# SUP_1V.net
KiCad netlist of a schematic drawn in Altium Designer
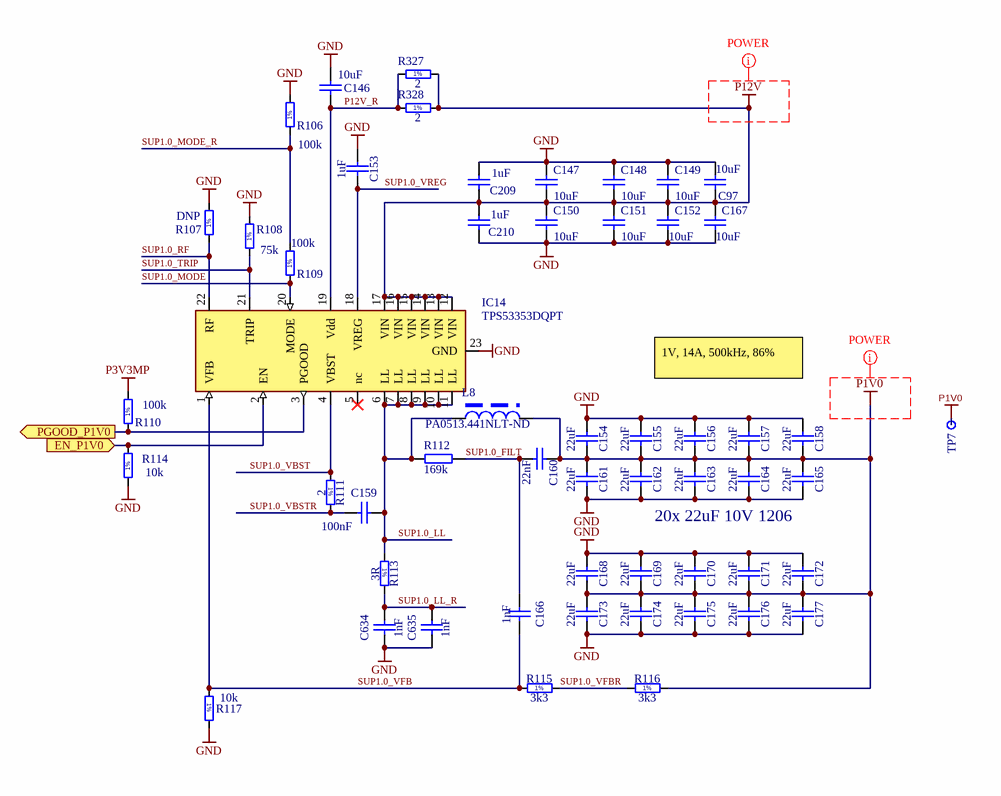
[diagram p0: SUP_1V.SchDoc]

(export (version "E")
  (design (tool "Eeschema 10.0.6"))
  (components
    (comp (ref "C97")
      (value "10uF")
      (footprint "CAPC2012X135N")
      (description "Non-polarised capacitor")
      (fields
        (field (name "PART NUMBER") "CC0805_10UF_16V_10%_X5R")
        (field (name "VOLTAGE") "16V")
        (field (name "AUTHOR") "CERN DEM JLC")
      )
      (libsource (lib "Capacitors") (part "Capacitor - non polarized"))
    )
    (comp (ref "C146")
      (value "10uF")
      (footprint "CAPC2012X135N")
      (description "Non-polarised capacitor")
      (fields
        (field (name "PART NUMBER") "CC0805_10UF_16V_10%_X5R")
        (field (name "VOLTAGE") "16V")
        (field (name "AUTHOR") "CERN DEM JLC")
      )
      (libsource (lib "Capacitors") (part "Capacitor - non polarized"))
    )
    (comp (ref "C147")
      (value "10uF")
      (footprint "CAPC2012X135N")
      (description "Non-polarised capacitor")
      (fields
        (field (name "PART NUMBER") "CC0805_10UF_16V_10%_X5R")
        (field (name "VOLTAGE") "16V")
        (field (name "AUTHOR") "CERN DEM JLC")
      )
      (libsource (lib "Capacitors") (part "Capacitor - non polarized"))
    )
    (comp (ref "C148")
      (value "10uF")
      (footprint "CAPC2012X135N")
      (description "Non-polarised capacitor")
      (fields
        (field (name "PART NUMBER") "CC0805_10UF_16V_10%_X5R")
        (field (name "VOLTAGE") "16V")
        (field (name "AUTHOR") "CERN DEM JLC")
      )
      (libsource (lib "Capacitors") (part "Capacitor - non polarized"))
    )
    (comp (ref "C149")
      (value "10uF")
      (footprint "CAPC2012X135N")
      (description "Non-polarised capacitor")
      (fields
        (field (name "PART NUMBER") "CC0805_10UF_16V_10%_X5R")
        (field (name "VOLTAGE") "16V")
        (field (name "AUTHOR") "CERN DEM JLC")
      )
      (libsource (lib "Capacitors") (part "Capacitor - non polarized"))
    )
    (comp (ref "C150")
      (value "10uF")
      (footprint "CAPC2012X135N")
      (description "Non-polarised capacitor")
      (fields
        (field (name "PART NUMBER") "CC0805_10UF_16V_10%_X5R")
        (field (name "VOLTAGE") "16V")
        (field (name "AUTHOR") "CERN DEM JLC")
      )
      (libsource (lib "Capacitors") (part "Capacitor - non polarized"))
    )
    (comp (ref "C151")
      (value "10uF")
      (footprint "CAPC2012X135N")
      (description "Non-polarised capacitor")
      (fields
        (field (name "PART NUMBER") "CC0805_10UF_16V_10%_X5R")
        (field (name "VOLTAGE") "16V")
        (field (name "AUTHOR") "CERN DEM JLC")
      )
      (libsource (lib "Capacitors") (part "Capacitor - non polarized"))
    )
    (comp (ref "C152")
      (value "10uF")
      (footprint "CAPC2012X135N")
      (description "Non-polarised capacitor")
      (fields
        (field (name "PART NUMBER") "CC0805_10UF_16V_10%_X5R")
        (field (name "VOLTAGE") "16V")
        (field (name "AUTHOR") "CERN DEM JLC")
      )
      (libsource (lib "Capacitors") (part "Capacitor - non polarized"))
    )
    (comp (ref "C153")
      (value "1uF")
      (footprint "CAPC1608X87N")
      (description "Non-polarised capacitor")
      (fields
        (field (name "PART NUMBER") "CC0603_1UF_16V_10%_X7R")
        (field (name "VOLTAGE") "16V")
        (field (name "AUTHOR") "CERN DEM JLC")
      )
      (libsource (lib "Capacitors") (part "Capacitor - non polarized"))
    )
    (comp (ref "C154")
      (value "22uF")
      (footprint "CAPC3216X180N")
      (description "Non-polarised capacitor")
      (fields
        (field (name "PART NUMBER") "CC1206_22UF_10V_10%_X7R")
        (field (name "VOLTAGE") "10V")
        (field (name "AUTHOR") "CERN DEM JLC")
      )
      (libsource (lib "Capacitors") (part "Capacitor - non polarized"))
    )
    (comp (ref "C155")
      (value "22uF")
      (footprint "CAPC3216X180N")
      (description "Non-polarised capacitor")
      (fields
        (field (name "PART NUMBER") "CC1206_22UF_10V_10%_X7R")
        (field (name "VOLTAGE") "10V")
        (field (name "AUTHOR") "CERN DEM JLC")
      )
      (libsource (lib "Capacitors") (part "Capacitor - non polarized"))
    )
    (comp (ref "C156")
      (value "22uF")
      (footprint "CAPC3216X180N")
      (description "Non-polarised capacitor")
      (fields
        (field (name "PART NUMBER") "CC1206_22UF_10V_10%_X7R")
        (field (name "VOLTAGE") "10V")
        (field (name "AUTHOR") "CERN DEM JLC")
      )
      (libsource (lib "Capacitors") (part "Capacitor - non polarized"))
    )
    (comp (ref "C157")
      (value "22uF")
      (footprint "CAPC3216X180N")
      (description "Non-polarised capacitor")
      (fields
        (field (name "PART NUMBER") "CC1206_22UF_10V_10%_X7R")
        (field (name "VOLTAGE") "10V")
        (field (name "AUTHOR") "CERN DEM JLC")
      )
      (libsource (lib "Capacitors") (part "Capacitor - non polarized"))
    )
    (comp (ref "C158")
      (value "22uF")
      (footprint "CAPC3216X180N")
      (description "Non-polarised capacitor")
      (fields
        (field (name "PART NUMBER") "CC1206_22UF_10V_10%_X7R")
        (field (name "VOLTAGE") "10V")
        (field (name "AUTHOR") "CERN DEM JLC")
      )
      (libsource (lib "Capacitors") (part "Capacitor - non polarized"))
    )
    (comp (ref "C159")
      (value "100nF")
      (footprint "CAPC1005X55N")
      (description "Non-polarised capacitor")
      (fields
        (field (name "PART NUMBER") "CC0402_100NF_16V_10%_X7R")
        (field (name "VOLTAGE") "16V")
        (field (name "AUTHOR") "CERN DEM JLC")
      )
      (libsource (lib "Capacitors") (part "Capacitor - non polarized"))
    )
    (comp (ref "C160")
      (value "22nF")
      (footprint "CAPC1608X87N")
      (description "Non-polarised capacitor")
      (fields
        (field (name "PART NUMBER") "CC0603_22NF_50V_10%_X7R")
        (field (name "VOLTAGE") "50V")
        (field (name "AUTHOR") "CERN DEM JLC")
      )
      (libsource (lib "Capacitors") (part "Capacitor - non polarized"))
    )
    (comp (ref "C161")
      (value "22uF")
      (footprint "CAPC3216X180N")
      (description "Non-polarised capacitor")
      (fields
        (field (name "PART NUMBER") "CC1206_22UF_10V_10%_X7R")
        (field (name "VOLTAGE") "10V")
        (field (name "AUTHOR") "CERN DEM JLC")
      )
      (libsource (lib "Capacitors") (part "Capacitor - non polarized"))
    )
    (comp (ref "C162")
      (value "22uF")
      (footprint "CAPC3216X180N")
      (description "Non-polarised capacitor")
      (fields
        (field (name "PART NUMBER") "CC1206_22UF_10V_10%_X7R")
        (field (name "VOLTAGE") "10V")
        (field (name "AUTHOR") "CERN DEM JLC")
      )
      (libsource (lib "Capacitors") (part "Capacitor - non polarized"))
    )
    (comp (ref "C163")
      (value "22uF")
      (footprint "CAPC3216X180N")
      (description "Non-polarised capacitor")
      (fields
        (field (name "PART NUMBER") "CC1206_22UF_10V_10%_X7R")
        (field (name "VOLTAGE") "10V")
        (field (name "AUTHOR") "CERN DEM JLC")
      )
      (libsource (lib "Capacitors") (part "Capacitor - non polarized"))
    )
    (comp (ref "C164")
      (value "22uF")
      (footprint "CAPC3216X180N")
      (description "Non-polarised capacitor")
      (fields
        (field (name "PART NUMBER") "CC1206_22UF_10V_10%_X7R")
        (field (name "VOLTAGE") "10V")
        (field (name "AUTHOR") "CERN DEM JLC")
      )
      (libsource (lib "Capacitors") (part "Capacitor - non polarized"))
    )
    (comp (ref "C165")
      (value "22uF")
      (footprint "CAPC3216X180N")
      (description "Non-polarised capacitor")
      (fields
        (field (name "PART NUMBER") "CC1206_22UF_10V_10%_X7R")
        (field (name "VOLTAGE") "10V")
        (field (name "AUTHOR") "CERN DEM JLC")
      )
      (libsource (lib "Capacitors") (part "Capacitor - non polarized"))
    )
    (comp (ref "C166")
      (value "1nF")
      (footprint "CAPC1005X55N")
      (description "Non-polarised capacitor")
      (fields
        (field (name "PART NUMBER") "CC0402_1NF_50V_10%_X7R")
        (field (name "VOLTAGE") "50V")
        (field (name "AUTHOR") "CERN DEM JLC")
      )
      (libsource (lib "Capacitors") (part "Capacitor - non polarized"))
    )
    (comp (ref "C167")
      (value "10uF")
      (footprint "CAPC2012X135N")
      (description "Non-polarised capacitor")
      (fields
        (field (name "PART NUMBER") "CC0805_10UF_16V_10%_X5R")
        (field (name "VOLTAGE") "16V")
        (field (name "AUTHOR") "CERN DEM JLC")
      )
      (libsource (lib "Capacitors") (part "Capacitor - non polarized"))
    )
    (comp (ref "C168")
      (value "22uF")
      (footprint "CAPC3216X180N")
      (description "Non-polarised capacitor")
      (fields
        (field (name "PART NUMBER") "CC1206_22UF_10V_10%_X7R")
        (field (name "VOLTAGE") "10V")
        (field (name "AUTHOR") "CERN DEM JLC")
      )
      (libsource (lib "Capacitors") (part "Capacitor - non polarized"))
    )
    (comp (ref "C169")
      (value "22uF")
      (footprint "CAPC3216X180N")
      (description "Non-polarised capacitor")
      (fields
        (field (name "PART NUMBER") "CC1206_22UF_10V_10%_X7R")
        (field (name "VOLTAGE") "10V")
        (field (name "AUTHOR") "CERN DEM JLC")
      )
      (libsource (lib "Capacitors") (part "Capacitor - non polarized"))
    )
    (comp (ref "C170")
      (value "22uF")
      (footprint "CAPC3216X180N")
      (description "Non-polarised capacitor")
      (fields
        (field (name "PART NUMBER") "CC1206_22UF_10V_10%_X7R")
        (field (name "VOLTAGE") "10V")
        (field (name "AUTHOR") "CERN DEM JLC")
      )
      (libsource (lib "Capacitors") (part "Capacitor - non polarized"))
    )
    (comp (ref "C171")
      (value "22uF")
      (footprint "CAPC3216X180N")
      (description "Non-polarised capacitor")
      (fields
        (field (name "PART NUMBER") "CC1206_22UF_10V_10%_X7R")
        (field (name "VOLTAGE") "10V")
        (field (name "AUTHOR") "CERN DEM JLC")
      )
      (libsource (lib "Capacitors") (part "Capacitor - non polarized"))
    )
    (comp (ref "C172")
      (value "22uF")
      (footprint "CAPC3216X180N")
      (description "Non-polarised capacitor")
      (fields
        (field (name "PART NUMBER") "CC1206_22UF_10V_10%_X7R")
        (field (name "VOLTAGE") "10V")
        (field (name "AUTHOR") "CERN DEM JLC")
      )
      (libsource (lib "Capacitors") (part "Capacitor - non polarized"))
    )
    (comp (ref "C173")
      (value "22uF")
      (footprint "CAPC3216X180N")
      (description "Non-polarised capacitor")
      (fields
        (field (name "PART NUMBER") "CC1206_22UF_10V_10%_X7R")
        (field (name "VOLTAGE") "10V")
        (field (name "AUTHOR") "CERN DEM JLC")
      )
      (libsource (lib "Capacitors") (part "Capacitor - non polarized"))
    )
    (comp (ref "C174")
      (value "22uF")
      (footprint "CAPC3216X180N")
      (description "Non-polarised capacitor")
      (fields
        (field (name "PART NUMBER") "CC1206_22UF_10V_10%_X7R")
        (field (name "VOLTAGE") "10V")
        (field (name "AUTHOR") "CERN DEM JLC")
      )
      (libsource (lib "Capacitors") (part "Capacitor - non polarized"))
    )
    (comp (ref "C175")
      (value "22uF")
      (footprint "CAPC3216X180N")
      (description "Non-polarised capacitor")
      (fields
        (field (name "PART NUMBER") "CC1206_22UF_10V_10%_X7R")
        (field (name "VOLTAGE") "10V")
        (field (name "AUTHOR") "CERN DEM JLC")
      )
      (libsource (lib "Capacitors") (part "Capacitor - non polarized"))
    )
    (comp (ref "C176")
      (value "22uF")
      (footprint "CAPC3216X180N")
      (description "Non-polarised capacitor")
      (fields
        (field (name "PART NUMBER") "CC1206_22UF_10V_10%_X7R")
        (field (name "VOLTAGE") "10V")
        (field (name "AUTHOR") "CERN DEM JLC")
      )
      (libsource (lib "Capacitors") (part "Capacitor - non polarized"))
    )
    (comp (ref "C177")
      (value "22uF")
      (footprint "CAPC3216X180N")
      (description "Non-polarised capacitor")
      (fields
        (field (name "PART NUMBER") "CC1206_22UF_10V_10%_X7R")
        (field (name "VOLTAGE") "10V")
        (field (name "AUTHOR") "CERN DEM JLC")
      )
      (libsource (lib "Capacitors") (part "Capacitor - non polarized"))
    )
    (comp (ref "C209")
      (value "1uF")
      (footprint "CAPC1608X87N")
      (description "Non-polarised capacitor")
      (fields
        (field (name "PART NUMBER") "CC0603_1UF_16V_10%_X7R")
        (field (name "VOLTAGE") "16V")
        (field (name "AUTHOR") "CERN DEM JLC")
      )
      (libsource (lib "Capacitors") (part "Capacitor - non polarized"))
    )
    (comp (ref "C210")
      (value "1uF")
      (footprint "CAPC1608X87N")
      (description "Non-polarised capacitor")
      (fields
        (field (name "PART NUMBER") "CC0603_1UF_16V_10%_X7R")
        (field (name "VOLTAGE") "16V")
        (field (name "AUTHOR") "CERN DEM JLC")
      )
      (libsource (lib "Capacitors") (part "Capacitor - non polarized"))
    )
    (comp (ref "C634")
      (value "1nF")
      (footprint "CAPC1005X55N")
      (description "Non-polarised capacitor")
      (fields
        (field (name "PART NUMBER") "CC0402_1NF_50V_10%_X7R")
        (field (name "VOLTAGE") "50V")
        (field (name "AUTHOR") "CERN DEM JLC")
      )
      (libsource (lib "Capacitors") (part "Capacitor - non polarized"))
    )
    (comp (ref "C635")
      (value "1nF")
      (footprint "CAPC1005X55N")
      (description "Non-polarised capacitor")
      (fields
        (field (name "PART NUMBER") "CC0402_1NF_50V_10%_X7R")
        (field (name "VOLTAGE") "50V")
        (field (name "AUTHOR") "CERN DEM JLC")
      )
      (libsource (lib "Capacitors") (part "Capacitor - non polarized"))
    )
    (comp (ref "IC14")
      (value "TPS53353DQPT")
      (footprint "LCCS50P600X500X150-22N")
      (description "High-Efficiency 20-A Synchronous Buck Converter with Eco-mode™")
      (libsource (lib "LIBRARY_SCH") (part "PM_TPS53353"))
    )
    (comp (ref "L8")
      (value "PA0513.441NLT-ND")
      (footprint "IND_PA0513")
      (description "440nH, 30A, 0.32mOhm")
      (libsource (lib "LIBRARY_SCH") (part "L_POWER_PA1513_440nH"))
    )
    (comp (ref "R106")
      (value "100k")
      (footprint "RESC1005X40N")
      (description "Resistor - 1%")
      (fields
        (field (name "PART NUMBER") "R0402_100K_1%_0.0625W_100PPM")
        (field (name "POWER") "0.0625W")
        (field (name "AUTHOR") "CERN DEM JLC")
      )
      (libsource (lib "Resistors") (part "Resistor - 1%"))
    )
    (comp (ref "R107")
      (value "DNP")
      (footprint "RESC1608X55N")
      (description "Resistor - 1%")
      (fields
        (field (name "PART NUMBER") "R0603_75K_1%_0.1W_100PPM")
        (field (name "POWER") "0.1W")
        (field (name "AUTHOR") "CERN DEM JLC")
      )
      (libsource (lib "Resistors") (part "Resistor - 1%"))
    )
    (comp (ref "R108")
      (value "75k")
      (footprint "RESC1608X55N")
      (description "Resistor - 1%")
      (fields
        (field (name "PART NUMBER") "R0603_75K_1%_0.1W_100PPM")
        (field (name "POWER") "0.1W")
        (field (name "AUTHOR") "CERN DEM JLC")
      )
      (libsource (lib "Resistors") (part "Resistor - 1%"))
    )
    (comp (ref "R109")
      (value "100k")
      (footprint "RESC1005X40N")
      (description "Resistor - 1%")
      (fields
        (field (name "PART NUMBER") "R0402_100K_1%_0.0625W_100PPM")
        (field (name "POWER") "0.0625W")
        (field (name "AUTHOR") "CERN DEM JLC")
      )
      (libsource (lib "Resistors") (part "Resistor - 1%"))
    )
    (comp (ref "R110")
      (value "100k")
      (footprint "RESC1005X40N")
      (description "Resistor - 1%")
      (fields
        (field (name "PART NUMBER") "R0402_100K_1%_0.0625W_100PPM")
        (field (name "POWER") "0.0625W")
        (field (name "AUTHOR") "CERN DEM JLC")
      )
      (libsource (lib "Resistors") (part "Resistor - 1%"))
    )
    (comp (ref "R111")
      (value "2")
      (footprint "RESC1608X55N")
      (description "Resistor - 1%")
      (fields
        (field (name "PART NUMBER") "R0603_2R_1%_0.1W_200PPM")
        (field (name "POWER") "0.1W")
        (field (name "AUTHOR") "CERN DEM JLC")
      )
      (libsource (lib "Resistors") (part "Resistor - 1%"))
    )
    (comp (ref "R112")
      (value "169k")
      (footprint "0603R")
      (description "SMD Resistor")
      (libsource (lib "LIBRARY_SCH") (part "RES_0603"))
    )
    (comp (ref "R113")
      (value "3R")
      (footprint "RESC3216X65N")
      (description "Resistor - 1%")
      (fields
        (field (name "PART NUMBER") "R1206_3R_1%_0.25W_200PPM")
        (field (name "POWER") "0.25W")
        (field (name "AUTHOR") "CERN DEM JLC")
      )
      (libsource (lib "Resistors") (part "Resistor - 1%"))
    )
    (comp (ref "R114")
      (value "10k")
      (footprint "RESC1005X40N")
      (description "Resistor - 1%")
      (fields
        (field (name "PART NUMBER") "R0402_10K_1%_0.0625W_100PPM")
        (field (name "POWER") "0.0625W")
        (field (name "AUTHOR") "CERN DEM JLC")
      )
      (libsource (lib "Resistors") (part "Resistor - 1%"))
    )
    (comp (ref "R115")
      (value "3k3")
      (footprint "RESC1608X55N")
      (description "Resistor - 1%")
      (fields
        (field (name "PART NUMBER") "R0603_3K3_1%_0.1W_100PPM")
        (field (name "POWER") "0.1W")
        (field (name "AUTHOR") "CERN DEM JLC")
      )
      (libsource (lib "Resistors") (part "Resistor - 1%"))
    )
    (comp (ref "R116")
      (value "3k3")
      (footprint "RESC1608X55N")
      (description "Resistor - 1%")
      (fields
        (field (name "PART NUMBER") "R0603_3K3_1%_0.1W_100PPM")
        (field (name "POWER") "0.1W")
        (field (name "AUTHOR") "CERN DEM JLC")
      )
      (libsource (lib "Resistors") (part "Resistor - 1%"))
    )
    (comp (ref "R117")
      (value "10k")
      (footprint "RESC1005X40N")
      (description "Resistor - 1%")
      (fields
        (field (name "PART NUMBER") "R0402_10K_1%_0.0625W_100PPM")
        (field (name "POWER") "0.0625W")
        (field (name "AUTHOR") "CERN DEM JLC")
      )
      (libsource (lib "Resistors") (part "Resistor - 1%"))
    )
    (comp (ref "R327")
      (value "2")
      (footprint "RESC1608X55N")
      (description "Resistor - 1%")
      (fields
        (field (name "PART NUMBER") "R0603_2R_1%_0.1W_200PPM")
        (field (name "POWER") "0.1W")
        (field (name "AUTHOR") "CERN DEM JLC")
      )
      (libsource (lib "Resistors") (part "Resistor - 1%"))
    )
    (comp (ref "R328")
      (value "2")
      (footprint "RESC1608X55N")
      (description "Resistor - 1%")
      (fields
        (field (name "PART NUMBER") "R0603_2R_1%_0.1W_200PPM")
        (field (name "POWER") "0.1W")
        (field (name "AUTHOR") "CERN DEM JLC")
      )
      (libsource (lib "Resistors") (part "Resistor - 1%"))
    )
    (comp (ref "TP7")
      (value "Test Point")
      (footprint "TPS127")
      (fields (field (name "PART NUMBER") "SMD_PAD_1.27X1.27MM") (field (name "AUTHOR") "CERN DEM JLC"))
      (libsource (lib "Eletro-mechanical") (part "Test Point"))
    )
  )
  (nets
    (net (code "1") (name "/EN_P1V0") (class "Default")
      (node (ref "IC14") (pin "2") (pinfunction "EN_2") (pintype "input"))
      (node (ref "R114") (pin "2") (pinfunction "2_2") (pintype "passive"))
    )
    (net (code "2") (name "/P12V_R") (class "Default")
      (node (ref "C146") (pin "1") (pinfunction "1_1") (pintype "passive"))
      (node (ref "IC14") (pin "19") (pinfunction "Vdd_19") (pintype "power_in"))
      (node (ref "R327") (pin "1") (pinfunction "1_1") (pintype "passive"))
      (node (ref "R328") (pin "1") (pinfunction "1_1") (pintype "passive"))
    )
    (net (code "3") (name "/PGOOD_P1V0") (class "Default")
      (node (ref "IC14") (pin "3") (pinfunction "PGOOD_3") (pintype "output"))
      (node (ref "R110") (pin "1") (pinfunction "1_1") (pintype "passive"))
    )
    (net (code "4") (name "/SUP1.0_FILT") (class "Default")
      (node (ref "C160") (pin "1") (pinfunction "1_1") (pintype "passive"))
      (node (ref "C166") (pin "2") (pinfunction "2_2") (pintype "passive"))
      (node (ref "R112") (pin "1") (pinfunction "1_1") (pintype "passive"))
    )
    (net (code "5") (name "/SUP1.0_LL") (class "Default")
      (node (ref "C159") (pin "1") (pinfunction "1_1") (pintype "passive"))
      (node (ref "IC14") (pin "10") (pinfunction "LL_10") (pintype "passive"))
      (node (ref "IC14") (pin "11") (pinfunction "LL_11") (pintype "passive"))
      (node (ref "IC14") (pin "6") (pinfunction "LL_6") (pintype "passive"))
      (node (ref "IC14") (pin "7") (pinfunction "LL_7") (pintype "passive"))
      (node (ref "IC14") (pin "8") (pinfunction "LL_8") (pintype "passive"))
      (node (ref "IC14") (pin "9") (pinfunction "LL_9") (pintype "passive"))
      (node (ref "L8") (pin "1") (pintype "passive"))
      (node (ref "R112") (pin "2") (pinfunction "2_2") (pintype "passive"))
      (node (ref "R113") (pin "1") (pinfunction "1_1") (pintype "passive"))
    )
    (net (code "6") (name "/SUP1.0_LL_R") (class "Default")
      (node (ref "C634") (pin "1") (pinfunction "1_1") (pintype "passive"))
      (node (ref "C635") (pin "1") (pinfunction "1_1") (pintype "passive"))
      (node (ref "R113") (pin "2") (pinfunction "2_2") (pintype "passive"))
    )
    (net (code "7") (name "/SUP1.0_MODE") (class "Default")
      (node (ref "IC14") (pin "20") (pinfunction "MODE_20") (pintype "input"))
      (node (ref "R109") (pin "1") (pinfunction "1_1") (pintype "passive"))
    )
    (net (code "8") (name "/SUP1.0_MODE_R") (class "Default")
      (node (ref "R106") (pin "1") (pinfunction "1_1") (pintype "passive"))
      (node (ref "R109") (pin "2") (pinfunction "2_2") (pintype "passive"))
    )
    (net (code "9") (name "/SUP1.0_RF") (class "Default")
      (node (ref "IC14") (pin "22") (pinfunction "RF_22") (pintype "passive"))
      (node (ref "R107") (pin "1") (pinfunction "1_1") (pintype "passive"))
    )
    (net (code "10") (name "/SUP1.0_TRIP") (class "Default")
      (node (ref "IC14") (pin "21") (pinfunction "TRIP_21") (pintype "passive"))
      (node (ref "R108") (pin "1") (pinfunction "1_1") (pintype "passive"))
    )
    (net (code "11") (name "/SUP1.0_VBST") (class "Default")
      (node (ref "IC14") (pin "4") (pinfunction "VBST_4") (pintype "passive"))
      (node (ref "R111") (pin "1") (pinfunction "1_1") (pintype "passive"))
    )
    (net (code "12") (name "/SUP1.0_VBSTR") (class "Default")
      (node (ref "C159") (pin "2") (pinfunction "2_2") (pintype "passive"))
      (node (ref "R111") (pin "2") (pinfunction "2_2") (pintype "passive"))
    )
    (net (code "13") (name "/SUP1.0_VFB") (class "Default")
      (node (ref "C166") (pin "1") (pinfunction "1_1") (pintype "passive"))
      (node (ref "IC14") (pin "1") (pinfunction "VFB_1") (pintype "input"))
      (node (ref "R115") (pin "1") (pinfunction "1_1") (pintype "passive"))
      (node (ref "R117") (pin "1") (pinfunction "1_1") (pintype "passive"))
    )
    (net (code "14") (name "/SUP1.0_VFBR") (class "Default")
      (node (ref "R115") (pin "2") (pinfunction "2_2") (pintype "passive"))
      (node (ref "R116") (pin "1") (pinfunction "1_1") (pintype "passive"))
    )
    (net (code "15") (name "/SUP1.0_VREG") (class "Default")
      (node (ref "C153") (pin "2") (pinfunction "2_2") (pintype "passive"))
      (node (ref "IC14") (pin "18") (pinfunction "VREG_18") (pintype "power_in"))
    )
    (net (code "16") (name "GND") (class "Default")
      (node (ref "C146") (pin "2") (pinfunction "2_2") (pintype "passive"))
      (node (ref "C147") (pin "2") (pinfunction "2_2") (pintype "passive"))
      (node (ref "C148") (pin "2") (pinfunction "2_2") (pintype "passive"))
      (node (ref "C149") (pin "2") (pinfunction "2_2") (pintype "passive"))
      (node (ref "C150") (pin "1") (pinfunction "1_1") (pintype "passive"))
      (node (ref "C151") (pin "1") (pinfunction "1_1") (pintype "passive"))
      (node (ref "C152") (pin "1") (pinfunction "1_1") (pintype "passive"))
      (node (ref "C153") (pin "1") (pinfunction "1_1") (pintype "passive"))
      (node (ref "C154") (pin "1") (pinfunction "1_1") (pintype "passive"))
      (node (ref "C155") (pin "1") (pinfunction "1_1") (pintype "passive"))
      (node (ref "C156") (pin "1") (pinfunction "1_1") (pintype "passive"))
      (node (ref "C157") (pin "1") (pinfunction "1_1") (pintype "passive"))
      (node (ref "C158") (pin "1") (pinfunction "1_1") (pintype "passive"))
      (node (ref "C161") (pin "2") (pinfunction "2_2") (pintype "passive"))
      (node (ref "C162") (pin "2") (pinfunction "2_2") (pintype "passive"))
      (node (ref "C163") (pin "2") (pinfunction "2_2") (pintype "passive"))
      (node (ref "C164") (pin "2") (pinfunction "2_2") (pintype "passive"))
      (node (ref "C165") (pin "2") (pinfunction "2_2") (pintype "passive"))
      (node (ref "C167") (pin "1") (pinfunction "1_1") (pintype "passive"))
      (node (ref "C168") (pin "1") (pinfunction "1_1") (pintype "passive"))
      (node (ref "C169") (pin "1") (pinfunction "1_1") (pintype "passive"))
      (node (ref "C170") (pin "1") (pinfunction "1_1") (pintype "passive"))
      (node (ref "C171") (pin "1") (pinfunction "1_1") (pintype "passive"))
      (node (ref "C172") (pin "1") (pinfunction "1_1") (pintype "passive"))
      (node (ref "C173") (pin "2") (pinfunction "2_2") (pintype "passive"))
      (node (ref "C174") (pin "2") (pinfunction "2_2") (pintype "passive"))
      (node (ref "C175") (pin "2") (pinfunction "2_2") (pintype "passive"))
      (node (ref "C176") (pin "2") (pinfunction "2_2") (pintype "passive"))
      (node (ref "C177") (pin "2") (pinfunction "2_2") (pintype "passive"))
      (node (ref "C209") (pin "2") (pinfunction "2_2") (pintype "passive"))
      (node (ref "C210") (pin "1") (pinfunction "1_1") (pintype "passive"))
      (node (ref "C634") (pin "2") (pinfunction "2_2") (pintype "passive"))
      (node (ref "C635") (pin "2") (pinfunction "2_2") (pintype "passive"))
      (node (ref "C97") (pin "1") (pinfunction "1_1") (pintype "passive"))
      (node (ref "IC14") (pin "23") (pinfunction "GND_23") (pintype "power_in"))
      (node (ref "R106") (pin "2") (pinfunction "2_2") (pintype "passive"))
      (node (ref "R107") (pin "2") (pinfunction "2_2") (pintype "passive"))
      (node (ref "R108") (pin "2") (pinfunction "2_2") (pintype "passive"))
      (node (ref "R114") (pin "1") (pinfunction "1_1") (pintype "passive"))
      (node (ref "R117") (pin "2") (pinfunction "2_2") (pintype "passive"))
    )
    (net (code "17") (name "P1V0") (class "Default")
      (node (ref "C154") (pin "2") (pinfunction "2_2") (pintype "passive"))
      (node (ref "C155") (pin "2") (pinfunction "2_2") (pintype "passive"))
      (node (ref "C156") (pin "2") (pinfunction "2_2") (pintype "passive"))
      (node (ref "C157") (pin "2") (pinfunction "2_2") (pintype "passive"))
      (node (ref "C158") (pin "2") (pinfunction "2_2") (pintype "passive"))
      (node (ref "C160") (pin "2") (pinfunction "2_2") (pintype "passive"))
      (node (ref "C161") (pin "1") (pinfunction "1_1") (pintype "passive"))
      (node (ref "C162") (pin "1") (pinfunction "1_1") (pintype "passive"))
      (node (ref "C163") (pin "1") (pinfunction "1_1") (pintype "passive"))
      (node (ref "C164") (pin "1") (pinfunction "1_1") (pintype "passive"))
      (node (ref "C165") (pin "1") (pinfunction "1_1") (pintype "passive"))
      (node (ref "C168") (pin "2") (pinfunction "2_2") (pintype "passive"))
      (node (ref "C169") (pin "2") (pinfunction "2_2") (pintype "passive"))
      (node (ref "C170") (pin "2") (pinfunction "2_2") (pintype "passive"))
      (node (ref "C171") (pin "2") (pinfunction "2_2") (pintype "passive"))
      (node (ref "C172") (pin "2") (pinfunction "2_2") (pintype "passive"))
      (node (ref "C173") (pin "1") (pinfunction "1_1") (pintype "passive"))
      (node (ref "C174") (pin "1") (pinfunction "1_1") (pintype "passive"))
      (node (ref "C175") (pin "1") (pinfunction "1_1") (pintype "passive"))
      (node (ref "C176") (pin "1") (pinfunction "1_1") (pintype "passive"))
      (node (ref "C177") (pin "1") (pinfunction "1_1") (pintype "passive"))
      (node (ref "L8") (pin "2") (pintype "passive"))
      (node (ref "R116") (pin "2") (pinfunction "2_2") (pintype "passive"))
      (node (ref "TP7") (pin "1") (pinfunction "1_1") (pintype "bidirectional"))
    )
    (net (code "18") (name "P3V3MP") (class "Default")
      (node (ref "R110") (pin "2") (pinfunction "2_2") (pintype "passive"))
    )
    (net (code "19") (name "P12V") (class "Default")
      (node (ref "C147") (pin "1") (pinfunction "1_1") (pintype "passive"))
      (node (ref "C148") (pin "1") (pinfunction "1_1") (pintype "passive"))
      (node (ref "C149") (pin "1") (pinfunction "1_1") (pintype "passive"))
      (node (ref "C150") (pin "2") (pinfunction "2_2") (pintype "passive"))
      (node (ref "C151") (pin "2") (pinfunction "2_2") (pintype "passive"))
      (node (ref "C152") (pin "2") (pinfunction "2_2") (pintype "passive"))
      (node (ref "C167") (pin "2") (pinfunction "2_2") (pintype "passive"))
      (node (ref "C209") (pin "1") (pinfunction "1_1") (pintype "passive"))
      (node (ref "C210") (pin "2") (pinfunction "2_2") (pintype "passive"))
      (node (ref "C97") (pin "2") (pinfunction "2_2") (pintype "passive"))
      (node (ref "IC14") (pin "12") (pinfunction "VIN_12") (pintype "power_in"))
      (node (ref "IC14") (pin "13") (pinfunction "VIN_13") (pintype "power_in"))
      (node (ref "IC14") (pin "14") (pinfunction "VIN_14") (pintype "power_in"))
      (node (ref "IC14") (pin "15") (pinfunction "VIN_15") (pintype "power_in"))
      (node (ref "IC14") (pin "16") (pinfunction "VIN_16") (pintype "power_in"))
      (node (ref "IC14") (pin "17") (pinfunction "VIN_17") (pintype "power_in"))
      (node (ref "R327") (pin "2") (pinfunction "2_2") (pintype "passive"))
      (node (ref "R328") (pin "2") (pinfunction "2_2") (pintype "passive"))
    )
    (net (code "20") (name "unconnected-(IC14-nc-Pad5)") (class "Default")
      (node (ref "IC14") (pin "5") (pinfunction "nc_5") (pintype "passive+no_connect"))
    )
  )
)
